# cryptostick-0v5.net
KiCad netlist of a schematic drawn in EAGLE
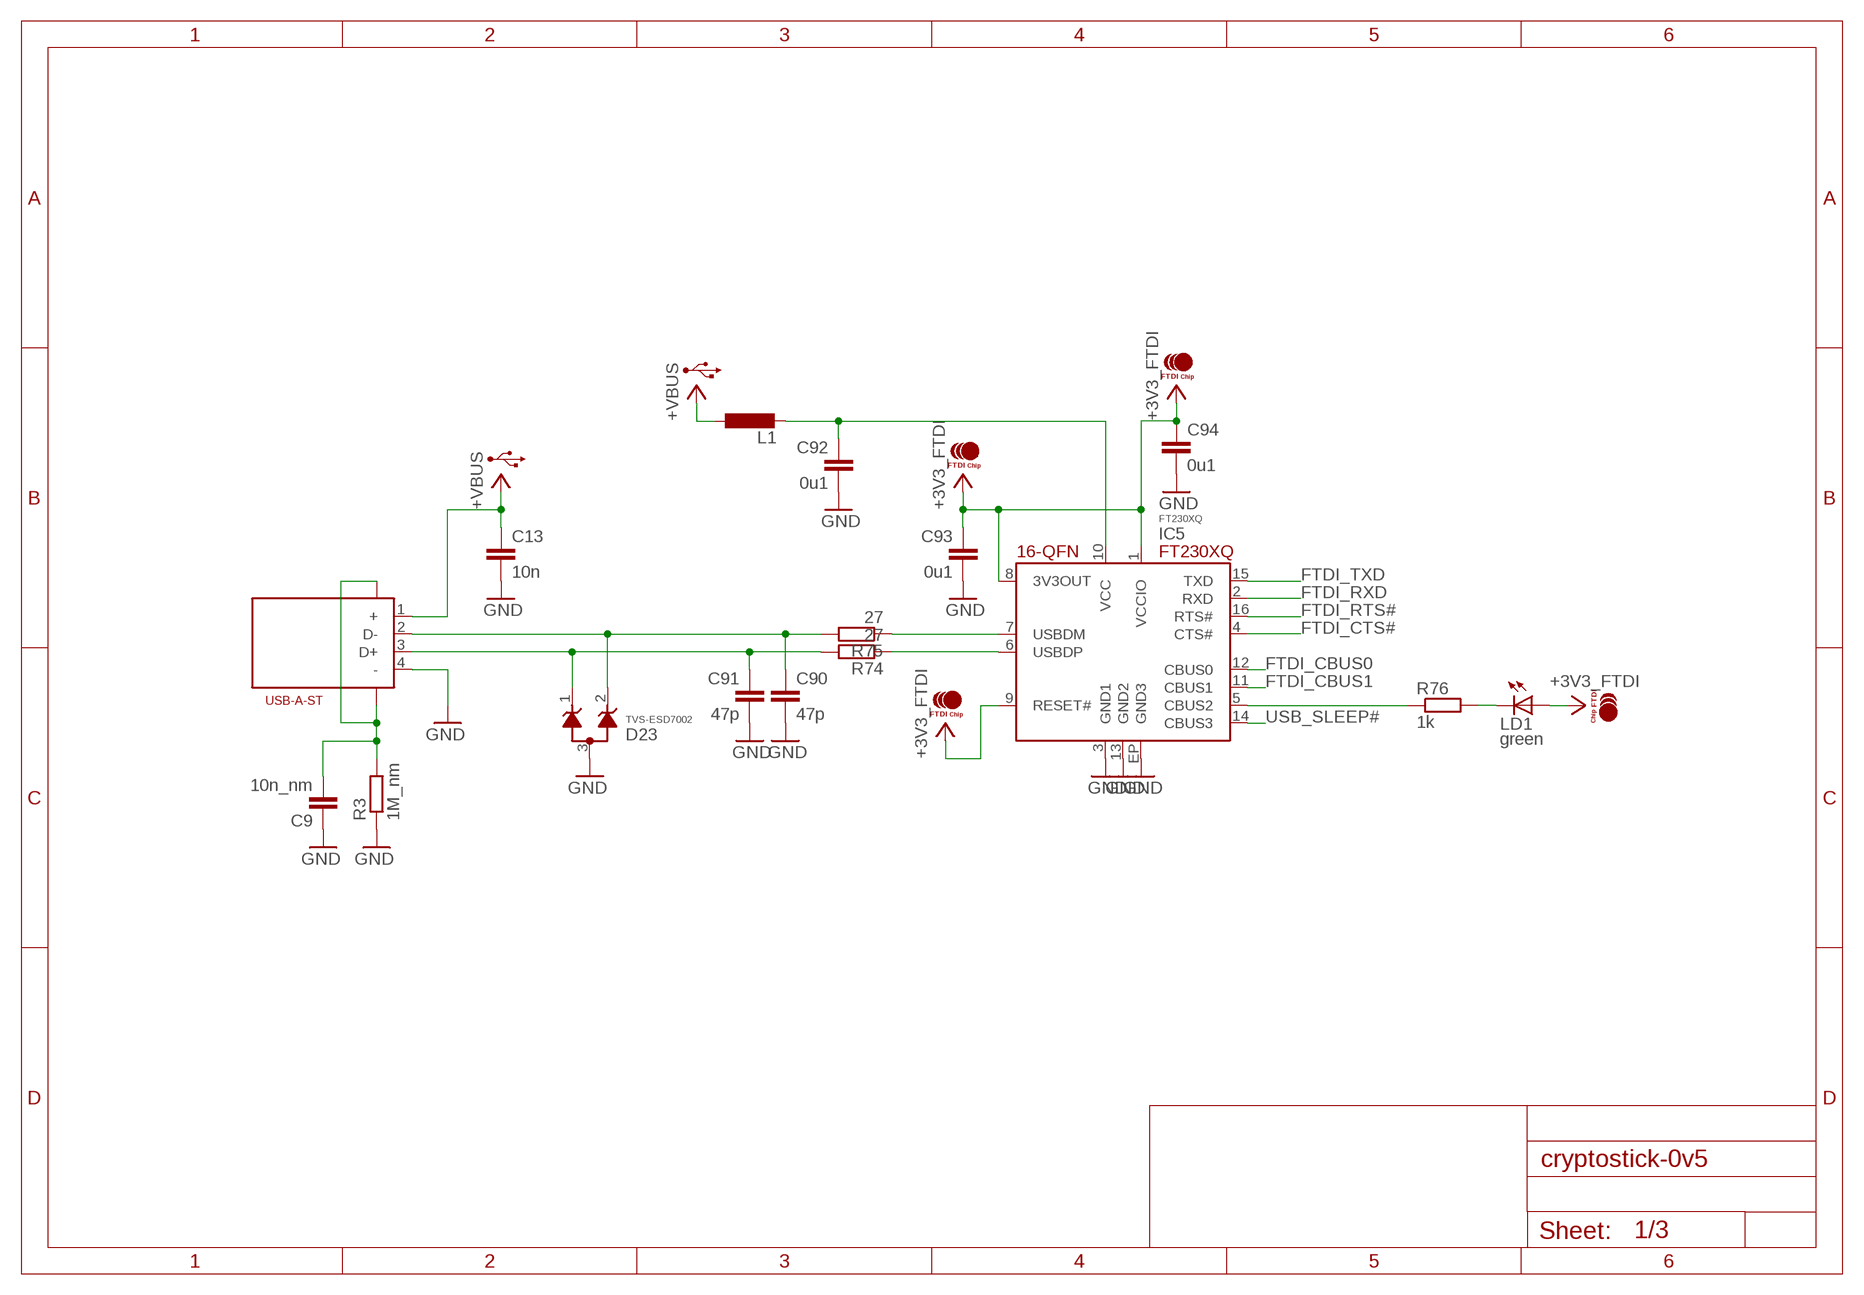
[diagram p0: schematic, sheet 1]
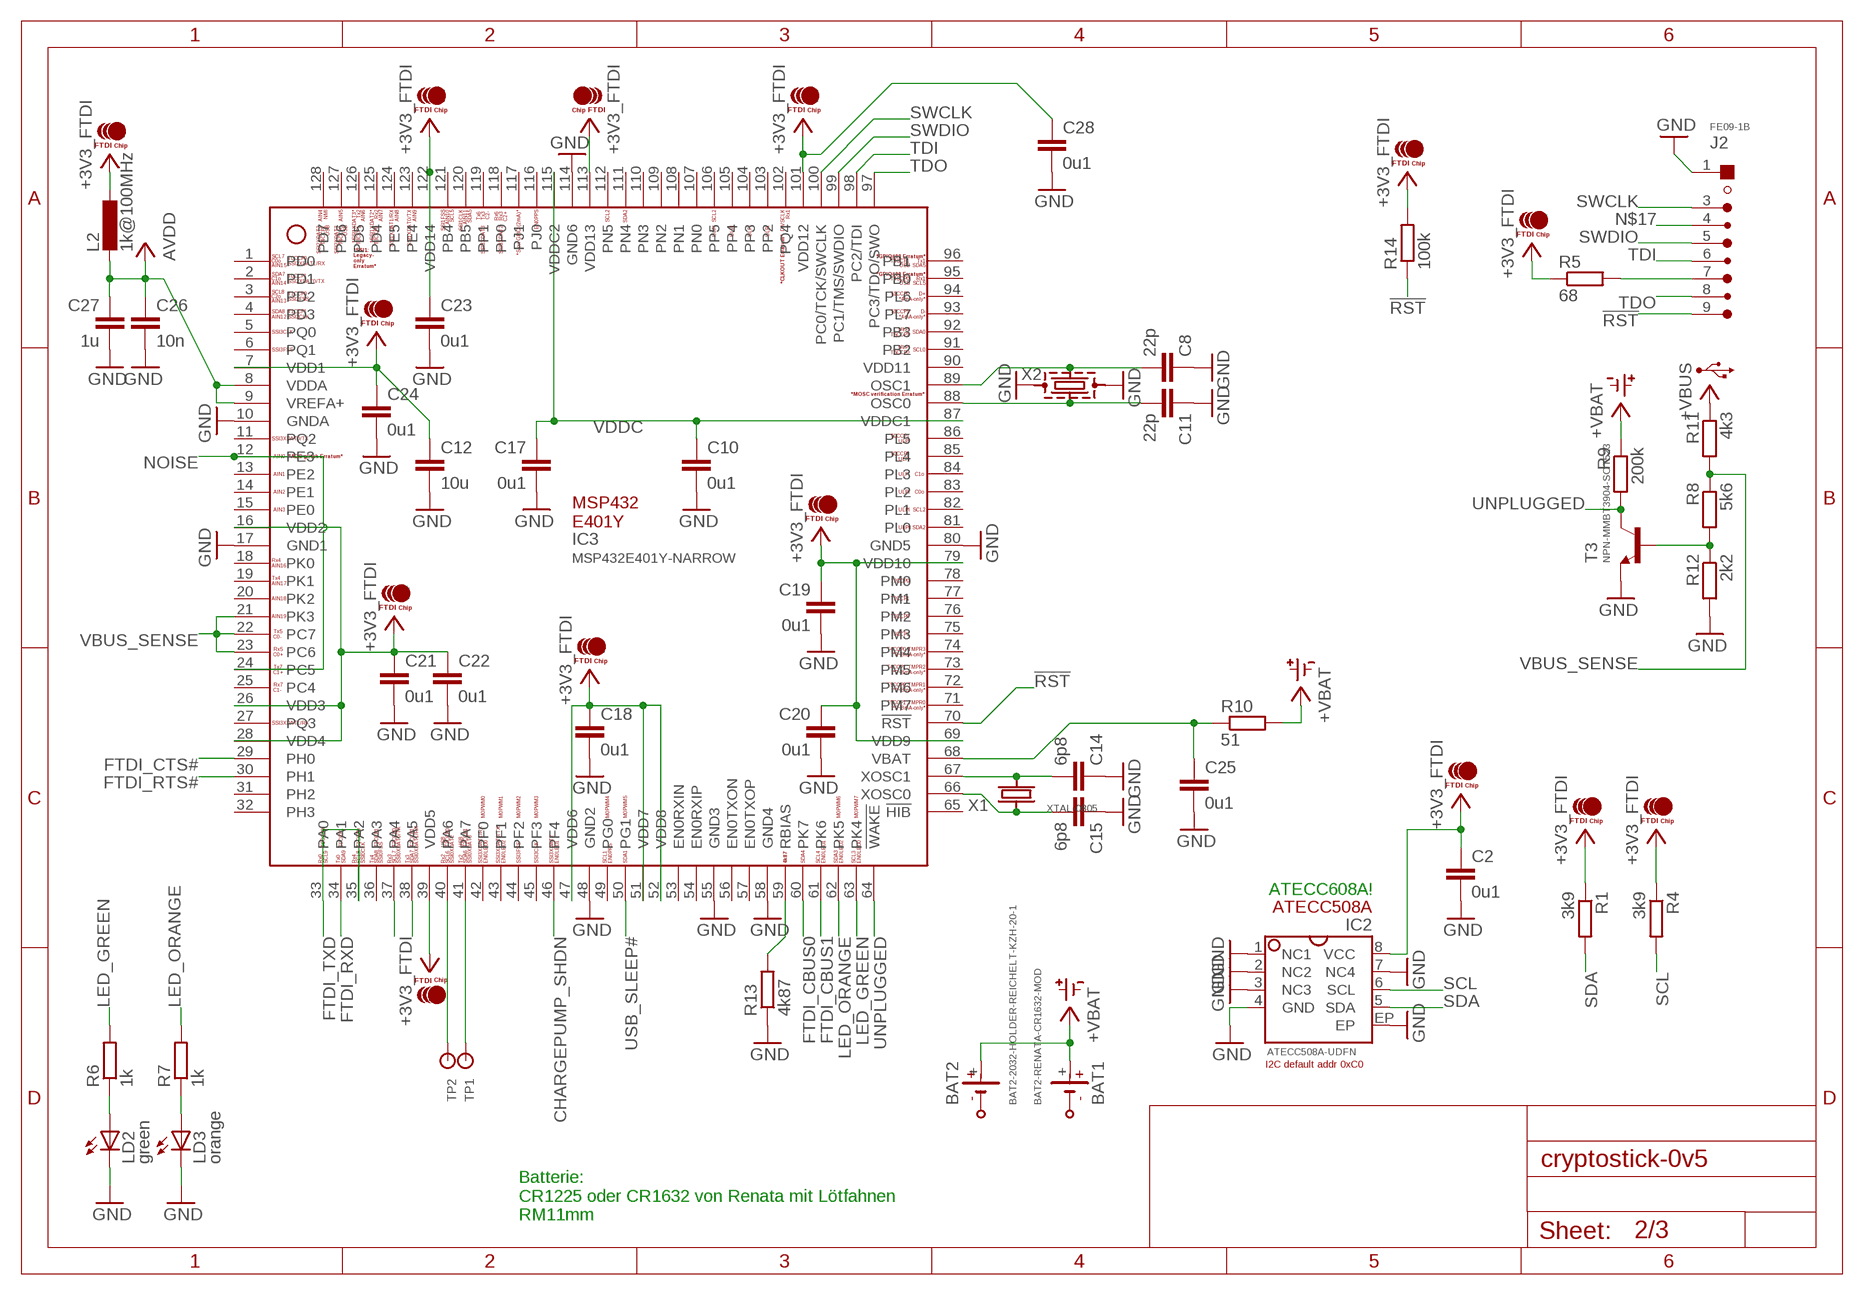
[diagram p1: schematic, sheet 2]
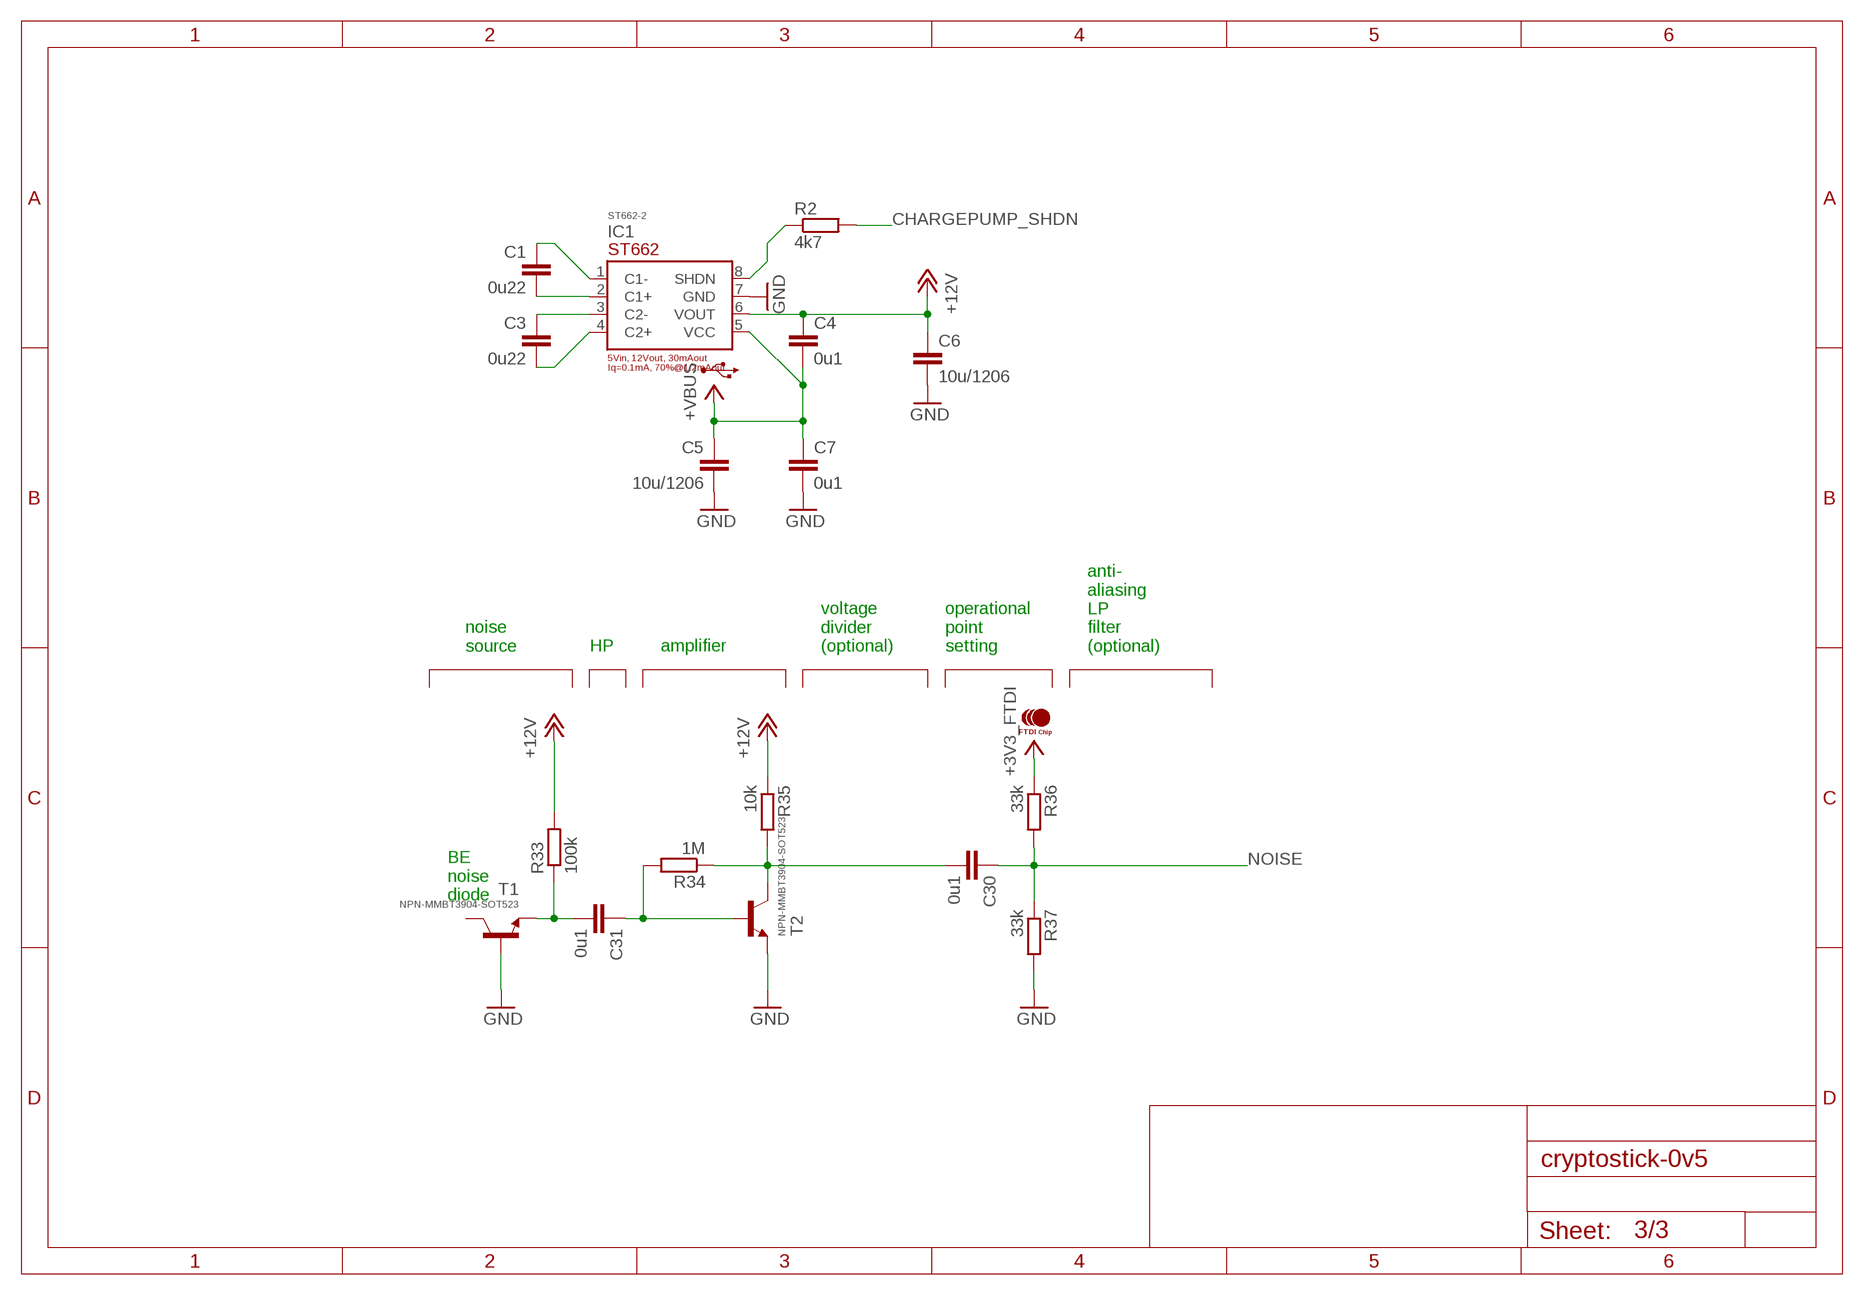
[diagram p2: schematic, sheet 3]

(export (version "E")
  (design (tool "Eeschema 10.0.6"))
  (components
    (comp (ref "C1")
      (value "0u22")
      (footprint "eagle-import:C0603")
      (libsource (lib "eagle-import") (part "C-EUC0603"))
    )
    (comp (ref "C3")
      (value "0u22")
      (footprint "eagle-import:C0603")
      (libsource (lib "eagle-import") (part "C-EUC0603"))
    )
    (comp (ref "C4")
      (value "0u1")
      (footprint "eagle-import:R0402-MCU")
      (libsource (lib "eagle-import") (part "C-EUR0402-MCU"))
    )
    (comp (ref "C5")
      (value "10u/1206")
      (footprint "eagle-import:C1206")
      (libsource (lib "eagle-import") (part "C-EUC1206"))
    )
    (comp (ref "C6")
      (value "10u/1206")
      (footprint "eagle-import:C1206")
      (libsource (lib "eagle-import") (part "C-EUC1206"))
    )
    (comp (ref "C7")
      (value "0u1")
      (footprint "eagle-import:R0402-MCU")
      (libsource (lib "eagle-import") (part "C-EUR0402-MCU"))
    )
    (comp (ref "C30")
      (value "0u1")
      (footprint "eagle-import:R0402-MCU")
      (libsource (lib "eagle-import") (part "C-EUR0402-MCU"))
    )
    (comp (ref "C31")
      (value "0u1")
      (footprint "eagle-import:R0402-MCU")
      (libsource (lib "eagle-import") (part "C-EUR0402-MCU"))
    )
    (comp (ref "IC1")
      (value "ST662-2")
      (footprint "eagle-import:8SOIC-2")
      (libsource (lib "eagle-import") (part "ST662-2"))
    )
    (comp (ref "R2")
      (value "4k7")
      (footprint "eagle-import:R0402-MCU")
      (libsource (lib "eagle-import") (part "R-EU_R0402-MCU"))
    )
    (comp (ref "R33")
      (value "100k")
      (footprint "eagle-import:R0402-MCU")
      (libsource (lib "eagle-import") (part "R-EU_R0402-MCU"))
    )
    (comp (ref "R34")
      (value "1M")
      (footprint "eagle-import:R0402-MCU")
      (libsource (lib "eagle-import") (part "R-EU_R0402-MCU"))
    )
    (comp (ref "R35")
      (value "10k")
      (footprint "eagle-import:R0402-MCU")
      (libsource (lib "eagle-import") (part "R-EU_R0402-MCU"))
    )
    (comp (ref "R36")
      (value "33k")
      (footprint "eagle-import:R0402-MCU")
      (libsource (lib "eagle-import") (part "R-EU_R0402-MCU"))
    )
    (comp (ref "R37")
      (value "33k")
      (footprint "eagle-import:R0402-MCU")
      (libsource (lib "eagle-import") (part "R-EU_R0402-MCU"))
    )
    (comp (ref "T1")
      (value "NPN-MMBT3904-SOT523")
      (footprint "eagle-import:SOT523")
      (libsource (lib "eagle-import") (part "NPN-MMBT3904-SOT523"))
    )
    (comp (ref "T2")
      (value "NPN-MMBT3904-SOT523")
      (footprint "eagle-import:SOT523")
      (libsource (lib "eagle-import") (part "NPN-MMBT3904-SOT523"))
    )
    (comp (ref "BAT1")
      (value "BAT2-RENATA-CR1632-MOD")
      (footprint "eagle-import:BAT2-RENATA-CR1632-MOD")
      (libsource (lib "eagle-import") (part "BAT2-RENATA-CR1632-MOD"))
    )
    (comp (ref "BAT2")
      (value "BAT2-2032-HOLDER-REICHELT-KZH-20-1")
      (footprint "eagle-import:BAT2-2032-HOLDER-REICHELT-KZH-20-1")
      (libsource (lib "eagle-import") (part "BAT2-2032-HOLDER-REICHELT-KZH-20-1"))
    )
    (comp (ref "C2")
      (value "0u1")
      (footprint "eagle-import:R0402-MCU")
      (libsource (lib "eagle-import") (part "C-EUR0402-MCU"))
    )
    (comp (ref "C8")
      (value "22p")
      (footprint "eagle-import:R0402-MCU")
      (libsource (lib "eagle-import") (part "C-EUR0402-MCU"))
    )
    (comp (ref "C10")
      (value "0u1")
      (footprint "eagle-import:R0402-MCU")
      (libsource (lib "eagle-import") (part "C-EUR0402-MCU"))
    )
    (comp (ref "C11")
      (value "22p")
      (footprint "eagle-import:R0402-MCU")
      (libsource (lib "eagle-import") (part "C-EUR0402-MCU"))
    )
    (comp (ref "C12")
      (value "10u")
      (footprint "eagle-import:R0603-MCU")
      (libsource (lib "eagle-import") (part "C-EUR0603-MCU"))
    )
    (comp (ref "C14")
      (value "6p8")
      (footprint "eagle-import:R0402-MCU")
      (libsource (lib "eagle-import") (part "C-EUR0402-MCU"))
    )
    (comp (ref "C15")
      (value "6p8")
      (footprint "eagle-import:R0402-MCU")
      (libsource (lib "eagle-import") (part "C-EUR0402-MCU"))
    )
    (comp (ref "C17")
      (value "0u1")
      (footprint "eagle-import:R0402-MCU")
      (libsource (lib "eagle-import") (part "C-EUR0402-MCU"))
    )
    (comp (ref "C18")
      (value "0u1")
      (footprint "eagle-import:R0402-MCU")
      (libsource (lib "eagle-import") (part "C-EUR0402-MCU"))
    )
    (comp (ref "C19")
      (value "0u1")
      (footprint "eagle-import:R0402-MCU")
      (libsource (lib "eagle-import") (part "C-EUR0402-MCU"))
    )
    (comp (ref "C20")
      (value "0u1")
      (footprint "eagle-import:R0402-MCU")
      (libsource (lib "eagle-import") (part "C-EUR0402-MCU"))
    )
    (comp (ref "C21")
      (value "0u1")
      (footprint "eagle-import:R0402-MCU")
      (libsource (lib "eagle-import") (part "C-EUR0402-MCU"))
    )
    (comp (ref "C22")
      (value "0u1")
      (footprint "eagle-import:R0402-MCU")
      (libsource (lib "eagle-import") (part "C-EUR0402-MCU"))
    )
    (comp (ref "C23")
      (value "0u1")
      (footprint "eagle-import:R0402-MCU")
      (libsource (lib "eagle-import") (part "C-EUR0402-MCU"))
    )
    (comp (ref "C24")
      (value "0u1")
      (footprint "eagle-import:R0402-MCU")
      (libsource (lib "eagle-import") (part "C-EUR0402-MCU"))
    )
    (comp (ref "C25")
      (value "0u1")
      (footprint "eagle-import:R0402-MCU")
      (libsource (lib "eagle-import") (part "C-EUR0402-MCU"))
    )
    (comp (ref "C26")
      (value "10n")
      (footprint "eagle-import:R0402-MCU")
      (libsource (lib "eagle-import") (part "C-EUR0402-MCU"))
    )
    (comp (ref "C27")
      (value "1u")
      (footprint "eagle-import:R0402-MCU")
      (libsource (lib "eagle-import") (part "C-EUR0402-MCU"))
    )
    (comp (ref "C28")
      (value "0u1")
      (footprint "eagle-import:R0402-MCU")
      (libsource (lib "eagle-import") (part "C-EUR0402-MCU"))
    )
    (comp (ref "IC2")
      (value "ATECC508A-UDFN")
      (footprint "eagle-import:8UDFN")
      (libsource (lib "eagle-import") (part "ATECC508A-UDFN"))
    )
    (comp (ref "IC3")
      (value "MSP432E401Y-NARROW")
      (footprint "eagle-import:128TQFP-MSP432E401Y-NARROW")
      (libsource (lib "eagle-import") (part "MSP432E401Y-NARROW"))
    )
    (comp (ref "J2")
      (value "FE09-1B")
      (footprint "eagle-import:FE09-1B")
      (libsource (lib "eagle-import") (part "FE09-1B"))
    )
    (comp (ref "L2")
      (value "1k@100MHz")
      (footprint "eagle-import:R0402-MCU")
      (libsource (lib "eagle-import") (part "L-EUR0402-MCU"))
    )
    (comp (ref "LD2")
      (value "green")
      (footprint "eagle-import:0603-SIDELED-RPI")
      (libsource (lib "eagle-import") (part "LED-0603-SIDELED-RPI"))
    )
    (comp (ref "LD3")
      (value "orange")
      (footprint "eagle-import:0603-SIDELED-RPI")
      (libsource (lib "eagle-import") (part "LED-0603-SIDELED-RPI"))
    )
    (comp (ref "R1")
      (value "3k9")
      (footprint "eagle-import:R0402-MCU")
      (libsource (lib "eagle-import") (part "R-EU_R0402-MCU"))
    )
    (comp (ref "R4")
      (value "3k9")
      (footprint "eagle-import:R0402-MCU")
      (libsource (lib "eagle-import") (part "R-EU_R0402-MCU"))
    )
    (comp (ref "R5")
      (value "68")
      (footprint "eagle-import:R0402-MCU")
      (libsource (lib "eagle-import") (part "R-EU_R0402-MCU"))
    )
    (comp (ref "R6")
      (value "1k")
      (footprint "eagle-import:R0402-MCU")
      (libsource (lib "eagle-import") (part "R-EU_R0402-MCU"))
    )
    (comp (ref "R7")
      (value "1k")
      (footprint "eagle-import:R0402-MCU")
      (libsource (lib "eagle-import") (part "R-EU_R0402-MCU"))
    )
    (comp (ref "R8")
      (value "5k6")
      (footprint "eagle-import:R0402-MCU")
      (libsource (lib "eagle-import") (part "R-EU_R0402-MCU"))
    )
    (comp (ref "R9")
      (value "200k")
      (footprint "eagle-import:R0402-MCU")
      (libsource (lib "eagle-import") (part "R-EU_R0402-MCU"))
    )
    (comp (ref "R10")
      (value "51")
      (footprint "eagle-import:R0402-MCU")
      (libsource (lib "eagle-import") (part "R-EU_R0402-MCU"))
    )
    (comp (ref "R11")
      (value "4k3")
      (footprint "eagle-import:R0402-MCU")
      (libsource (lib "eagle-import") (part "R-EU_R0402-MCU"))
    )
    (comp (ref "R12")
      (value "2k2")
      (footprint "eagle-import:R0402-MCU")
      (libsource (lib "eagle-import") (part "R-EU_R0402-MCU"))
    )
    (comp (ref "R13")
      (value "4k87")
      (footprint "eagle-import:R0402-MCU")
      (libsource (lib "eagle-import") (part "R-EU_R0402-MCU"))
    )
    (comp (ref "R14")
      (value "100k")
      (footprint "eagle-import:R0402-MCU")
      (libsource (lib "eagle-import") (part "R-EU_R0402-MCU"))
    )
    (comp (ref "T3")
      (value "NPN-MMBT3904-SOT523")
      (footprint "eagle-import:SOT523")
      (libsource (lib "eagle-import") (part "NPN-MMBT3904-SOT523"))
    )
    (comp (ref "TP1")
      (value "TP-SMT-1.5MM")
      (footprint "eagle-import:TP-SMT-1.5MM")
      (libsource (lib "eagle-import") (part "TP-SMT-1.5MM"))
    )
    (comp (ref "TP2")
      (value "TP-SMT-1.5MM")
      (footprint "eagle-import:TP-SMT-1.5MM")
      (libsource (lib "eagle-import") (part "TP-SMT-1.5MM"))
    )
    (comp (ref "X1")
      (value "XTAL-0805")
      (footprint "eagle-import:XTAL-32KHZ-0805")
      (libsource (lib "eagle-import") (part "XTAL-0805"))
    )
    (comp (ref "X2")
      (value "XTAL-2.0X1.6-MOD")
      (footprint "eagle-import:XTAL-2.0X1.6-MOD")
      (libsource (lib "eagle-import") (part "XTAL-2.0X1.6-MOD"))
    )
    (comp (ref "C9")
      (value "10n_nm")
      (footprint "eagle-import:C0603")
      (libsource (lib "eagle-import") (part "C-EUC0603"))
    )
    (comp (ref "C13")
      (value "10n")
      (footprint "eagle-import:R0402-MCU")
      (libsource (lib "eagle-import") (part "C-EUR0402-MCU"))
    )
    (comp (ref "C90")
      (value "47p")
      (footprint "eagle-import:R0402-MCU")
      (libsource (lib "eagle-import") (part "C-EUR0402-MCU"))
    )
    (comp (ref "C91")
      (value "47p")
      (footprint "eagle-import:R0402-MCU")
      (libsource (lib "eagle-import") (part "C-EUR0402-MCU"))
    )
    (comp (ref "C92")
      (value "0u1")
      (footprint "eagle-import:R0402-MCU")
      (libsource (lib "eagle-import") (part "C-EUR0402-MCU"))
    )
    (comp (ref "C93")
      (value "0u1")
      (footprint "eagle-import:R0402-MCU")
      (libsource (lib "eagle-import") (part "C-EUR0402-MCU"))
    )
    (comp (ref "C94")
      (value "0u1")
      (footprint "eagle-import:R0402-MCU")
      (libsource (lib "eagle-import") (part "C-EUR0402-MCU"))
    )
    (comp (ref "D23")
      (value "TVS-ESD7002")
      (footprint "eagle-import:SC70-3")
      (libsource (lib "eagle-import") (part "TVS-ESD7002"))
    )
    (comp (ref "IC5")
      (value "FT230XQ")
      (footprint "eagle-import:16QFN-FT230X")
      (libsource (lib "eagle-import") (part "FT230XQ"))
    )
    (comp (ref "J1")
      (value "USB-A-ST")
      (footprint "eagle-import:USB-A-ST")
      (libsource (lib "eagle-import") (part "USB-A-ST"))
    )
    (comp (ref "L1")
      (value "L-EUR0402-MCU")
      (footprint "eagle-import:R0402-MCU")
      (libsource (lib "eagle-import") (part "L-EUR0402-MCU"))
    )
    (comp (ref "LD1")
      (value "green")
      (footprint "eagle-import:0603-SIDELED-RPI")
      (libsource (lib "eagle-import") (part "LED-0603-SIDELED-RPI"))
    )
    (comp (ref "R3")
      (value "1M_nm")
      (footprint "eagle-import:R0603")
      (libsource (lib "eagle-import") (part "R-EU_R0603"))
    )
    (comp (ref "R74")
      (value "27")
      (footprint "eagle-import:R0402-MCU")
      (libsource (lib "eagle-import") (part "R-EU_R0402-MCU"))
    )
    (comp (ref "R75")
      (value "27")
      (footprint "eagle-import:R0402-MCU")
      (libsource (lib "eagle-import") (part "R-EU_R0402-MCU"))
    )
    (comp (ref "R76")
      (value "1k")
      (footprint "eagle-import:R0402-MCU")
      (libsource (lib "eagle-import") (part "R-EU_R0402-MCU"))
    )
  )
  (nets
    (net (code "1") (name "+3V3_FTDI") (class "Default")
      (node (ref "C12") (pin "1") (pinfunction "1_1") (pintype "passive"))
      (node (ref "C18") (pin "1") (pinfunction "1_1") (pintype "passive"))
      (node (ref "C19") (pin "1") (pinfunction "1_1") (pintype "passive"))
      (node (ref "C2") (pin "1") (pinfunction "1_1") (pintype "passive"))
      (node (ref "C20") (pin "1") (pinfunction "1_1") (pintype "passive"))
      (node (ref "C21") (pin "1") (pinfunction "1_1") (pintype "passive"))
      (node (ref "C22") (pin "1") (pinfunction "1_1") (pintype "passive"))
      (node (ref "C23") (pin "1") (pinfunction "1_1") (pintype "passive"))
      (node (ref "C24") (pin "1") (pinfunction "1_1") (pintype "passive"))
      (node (ref "C28") (pin "1") (pinfunction "1_1") (pintype "passive"))
      (node (ref "C93") (pin "1") (pinfunction "1_1") (pintype "passive"))
      (node (ref "C94") (pin "1") (pinfunction "1_1") (pintype "passive"))
      (node (ref "IC2") (pin "8") (pinfunction "VCC_8") (pintype "bidirectional"))
      (node (ref "IC3") (pin "101") (pinfunction "VDD12_101") (pintype "bidirectional"))
      (node (ref "IC3") (pin "113") (pinfunction "VDD13_113") (pintype "bidirectional"))
      (node (ref "IC3") (pin "122") (pinfunction "VDD14_122") (pintype "bidirectional"))
      (node (ref "IC3") (pin "16") (pinfunction "VDD2_16") (pintype "bidirectional"))
      (node (ref "IC3") (pin "26") (pinfunction "VDD3_26") (pintype "bidirectional"))
      (node (ref "IC3") (pin "28") (pinfunction "VDD4_28") (pintype "bidirectional"))
      (node (ref "IC3") (pin "39") (pinfunction "VDD5_39") (pintype "bidirectional"))
      (node (ref "IC3") (pin "47") (pinfunction "VDD6_47") (pintype "bidirectional"))
      (node (ref "IC3") (pin "51") (pinfunction "VDD7_51") (pintype "bidirectional"))
      (node (ref "IC3") (pin "52") (pinfunction "VDD8_52") (pintype "bidirectional"))
      (node (ref "IC3") (pin "69") (pinfunction "VDD9_69") (pintype "bidirectional"))
      (node (ref "IC3") (pin "7") (pinfunction "VDD1_7") (pintype "bidirectional"))
      (node (ref "IC3") (pin "79") (pinfunction "VDD10_79") (pintype "bidirectional"))
      (node (ref "IC5") (pin "1") (pinfunction "VCCIO_1") (pintype "bidirectional"))
      (node (ref "IC5") (pin "8") (pinfunction "3V3OUT_8") (pintype "bidirectional"))
      (node (ref "IC5") (pin "9") (pinfunction "RESET#_9") (pintype "bidirectional"))
      (node (ref "L2") (pin "1") (pinfunction "1_1") (pintype "passive"))
      (node (ref "LD1") (pin "A") (pinfunction "A_A") (pintype "passive"))
      (node (ref "R1") (pin "1") (pinfunction "1_1") (pintype "passive"))
      (node (ref "R14") (pin "2") (pinfunction "2_2") (pintype "passive"))
      (node (ref "R36") (pin "1") (pinfunction "1_1") (pintype "passive"))
      (node (ref "R4") (pin "1") (pinfunction "1_1") (pintype "passive"))
      (node (ref "R5") (pin "1") (pinfunction "1_1") (pintype "passive"))
    )
    (net (code "2") (name "+12V") (class "Default")
      (node (ref "C4") (pin "1") (pinfunction "1_1") (pintype "passive"))
      (node (ref "C6") (pin "1") (pinfunction "1_1") (pintype "passive"))
      (node (ref "IC1") (pin "6") (pinfunction "VOUT_6") (pintype "bidirectional"))
      (node (ref "R33") (pin "2") (pinfunction "2_2") (pintype "passive"))
      (node (ref "R35") (pin "1") (pinfunction "1_1") (pintype "passive"))
    )
    (net (code "3") (name "+VBAT") (class "Default")
      (node (ref "BAT1") (pin "+") (pinfunction "+_+") (pintype "bidirectional"))
      (node (ref "BAT2") (pin "+") (pinfunction "+_+") (pintype "bidirectional"))
      (node (ref "R10") (pin "2") (pinfunction "2_2") (pintype "passive"))
      (node (ref "R9") (pin "1") (pinfunction "1_1") (pintype "passive"))
    )
    (net (code "4") (name "+VBUS") (class "Default")
      (node (ref "C13") (pin "1") (pinfunction "1_1") (pintype "passive"))
      (node (ref "C4") (pin "2") (pinfunction "2_2") (pintype "passive"))
      (node (ref "C5") (pin "1") (pinfunction "1_1") (pintype "passive"))
      (node (ref "C7") (pin "1") (pinfunction "1_1") (pintype "passive"))
      (node (ref "IC1") (pin "5") (pinfunction "VCC_5") (pintype "bidirectional"))
      (node (ref "J1") (pin "1") (pinfunction "+_1") (pintype "bidirectional"))
      (node (ref "L1") (pin "1") (pinfunction "1_1") (pintype "passive"))
      (node (ref "R11") (pin "1") (pinfunction "1_1") (pintype "passive"))
    )
    (net (code "5") (name "AVDD") (class "Default")
      (node (ref "C26") (pin "1") (pinfunction "1_1") (pintype "passive"))
      (node (ref "C27") (pin "1") (pinfunction "1_1") (pintype "passive"))
      (node (ref "IC3") (pin "8") (pinfunction "VDDA_8") (pintype "bidirectional"))
      (node (ref "IC3") (pin "9") (pinfunction "VREFA+_9") (pintype "bidirectional"))
      (node (ref "L2") (pin "2") (pinfunction "2_2") (pintype "passive"))
    )
    (net (code "6") (name "CHARGEPUMP_SHDN") (class "Default")
      (node (ref "IC3") (pin "46") (pinfunction "PF4_46") (pintype "bidirectional"))
      (node (ref "R2") (pin "2") (pinfunction "2_2") (pintype "passive"))
    )
    (net (code "7") (name "DBG_RXD") (class "Default")
      (node (ref "IC3") (pin "40") (pinfunction "PA6_40") (pintype "bidirectional"))
      (node (ref "IC3") (pin "74") (pinfunction "PM4_74") (pintype "bidirectional"))
      (node (ref "TP2") (pin "1") (pinfunction "1_1") (pintype "bidirectional"))
    )
    (net (code "8") (name "DBG_TXD") (class "Default")
      (node (ref "IC3") (pin "41") (pinfunction "PA7_41") (pintype "bidirectional"))
      (node (ref "IC3") (pin "73") (pinfunction "PM5_73") (pintype "bidirectional"))
      (node (ref "TP1") (pin "1") (pinfunction "1_1") (pintype "bidirectional"))
    )
    (net (code "9") (name "FTDI_CBUS0") (class "Default")
      (node (ref "IC3") (pin "60") (pinfunction "PK7_60") (pintype "bidirectional"))
      (node (ref "IC5") (pin "12") (pinfunction "CBUS0_12") (pintype "bidirectional"))
    )
    (net (code "10") (name "FTDI_CBUS1") (class "Default")
      (node (ref "IC3") (pin "61") (pinfunction "PK6_61") (pintype "bidirectional"))
      (node (ref "IC5") (pin "11") (pinfunction "CBUS1_11") (pintype "bidirectional"))
    )
    (net (code "11") (name "FTDI_CTS#") (class "Default")
      (node (ref "IC3") (pin "29") (pinfunction "PH0_29") (pintype "bidirectional"))
      (node (ref "IC5") (pin "4") (pinfunction "CTS#_4") (pintype "bidirectional"))
    )
    (net (code "12") (name "FTDI_RTS#") (class "Default")
      (node (ref "IC3") (pin "30") (pinfunction "PH1_30") (pintype "bidirectional"))
      (node (ref "IC5") (pin "16") (pinfunction "RTS#_16") (pintype "bidirectional"))
    )
    (net (code "13") (name "FTDI_RXD") (class "Default")
      (node (ref "IC3") (pin "34") (pinfunction "PA1_34") (pintype "bidirectional"))
      (node (ref "IC5") (pin "2") (pinfunction "RXD_2") (pintype "bidirectional"))
    )
    (net (code "14") (name "FTDI_TXD") (class "Default")
      (node (ref "IC3") (pin "33") (pinfunction "PA0_33") (pintype "bidirectional"))
      (node (ref "IC3") (pin "35") (pinfunction "PA2_35") (pintype "bidirectional"))
      (node (ref "IC5") (pin "15") (pinfunction "TXD_15") (pintype "bidirectional"))
    )
    (net (code "15") (name "GND") (class "Default")
      (node (ref "C10") (pin "2") (pinfunction "2_2") (pintype "passive"))
      (node (ref "C11") (pin "1") (pinfunction "1_1") (pintype "passive"))
      (node (ref "C12") (pin "2") (pinfunction "2_2") (pintype "passive"))
      (node (ref "C13") (pin "2") (pinfunction "2_2") (pintype "passive"))
      (node (ref "C14") (pin "1") (pinfunction "1_1") (pintype "passive"))
      (node (ref "C15") (pin "1") (pinfunction "1_1") (pintype "passive"))
      (node (ref "C17") (pin "2") (pinfunction "2_2") (pintype "passive"))
      (node (ref "C18") (pin "2") (pinfunction "2_2") (pintype "passive"))
      (node (ref "C19") (pin "2") (pinfunction "2_2") (pintype "passive"))
      (node (ref "C2") (pin "2") (pinfunction "2_2") (pintype "passive"))
      (node (ref "C20") (pin "2") (pinfunction "2_2") (pintype "passive"))
      (node (ref "C21") (pin "2") (pinfunction "2_2") (pintype "passive"))
      (node (ref "C22") (pin "2") (pinfunction "2_2") (pintype "passive"))
      (node (ref "C23") (pin "2") (pinfunction "2_2") (pintype "passive"))
      (node (ref "C24") (pin "2") (pinfunction "2_2") (pintype "passive"))
      (node (ref "C25") (pin "2") (pinfunction "2_2") (pintype "passive"))
      (node (ref "C26") (pin "2") (pinfunction "2_2") (pintype "passive"))
      (node (ref "C27") (pin "2") (pinfunction "2_2") (pintype "passive"))
      (node (ref "C28") (pin "2") (pinfunction "2_2") (pintype "passive"))
      (node (ref "C5") (pin "2") (pinfunction "2_2") (pintype "passive"))
      (node (ref "C6") (pin "2") (pinfunction "2_2") (pintype "passive"))
      (node (ref "C7") (pin "2") (pinfunction "2_2") (pintype "passive"))
      (node (ref "C8") (pin "1") (pinfunction "1_1") (pintype "passive"))
      (node (ref "C9") (pin "1") (pinfunction "1_1") (pintype "passive"))
      (node (ref "C90") (pin "2") (pinfunction "2_2") (pintype "passive"))
      (node (ref "C91") (pin "2") (pinfunction "2_2") (pintype "passive"))
      (node (ref "C92") (pin "2") (pinfunction "2_2") (pintype "passive"))
      (node (ref "C93") (pin "2") (pinfunction "2_2") (pintype "passive"))
      (node (ref "C94") (pin "2") (pinfunction "2_2") (pintype "passive"))
      (node (ref "D23") (pin "3") (pinfunction "3_3") (pintype "bidirectional"))
      (node (ref "IC1") (pin "7") (pinfunction "GND_7") (pintype "bidirectional"))
      (node (ref "IC2") (pin "1") (pinfunction "NC1_1") (pintype "bidirectional"))
      (node (ref "IC2") (pin "2") (pinfunction "NC2_2") (pintype "bidirectional"))
      (node (ref "IC2") (pin "3") (pinfunction "NC3_3") (pintype "bidirectional"))
      (node (ref "IC2") (pin "4") (pinfunction "GND_4") (pintype "bidirectional"))
      (node (ref "IC2") (pin "7") (pinfunction "NC4_7") (pintype "bidirectional"))
      (node (ref "IC2") (pin "EP") (pinfunction "EP_EP") (pintype "bidirectional"))
      (node (ref "IC3") (pin "10") (pinfunction "GNDA_10") (pintype "bidirectional"))
      (node (ref "IC3") (pin "114") (pinfunction "GND6_114") (pintype "bidirectional"))
      (node (ref "IC3") (pin "17") (pinfunction "GND1_17") (pintype "bidirectional"))
      (node (ref "IC3") (pin "48") (pinfunction "GND2_48") (pintype "bidirectional"))
      (node (ref "IC3") (pin "55") (pinfunction "GND3_55") (pintype "bidirectional"))
      (node (ref "IC3") (pin "58") (pinfunction "GND4_58") (pintype "bidirectional"))
      (node (ref "IC3") (pin "80") (pinfunction "GND5_80") (pintype "bidirectional"))
      (node (ref "IC5") (pin "13") (pinfunction "GND2_13") (pintype "bidirectional"))
      (node (ref "IC5") (pin "3") (pinfunction "GND1_3") (pintype "bidirectional"))
      (node (ref "IC5") (pin "EP") (pinfunction "GND3_EP") (pintype "bidirectional"))
      (node (ref "J1") (pin "4") (pinfunction "-_4") (pintype "bidirectional"))
      (node (ref "J2") (pin "1") (pinfunction "1_1") (pintype "bidirectional"))
      (node (ref "LD2") (pin "C") (pinfunction "C_C") (pintype "passive"))
      (node (ref "LD3") (pin "C") (pinfunction "C_C") (pintype "passive"))
      (node (ref "R12") (pin "2") (pinfunction "2_2") (pintype "passive"))
      (node (ref "R13") (pin "1") (pinfunction "1_1") (pintype "passive"))
      (node (ref "R3") (pin "1") (pinfunction "1_1") (pintype "passive"))
      (node (ref "R37") (pin "2") (pinfunction "2_2") (pintype "passive"))
      (node (ref "T1") (pin "1") (pinfunction "B_1") (pintype "passive"))
      (node (ref "T2") (pin "2") (pinfunction "E_2") (pintype "passive"))
      (node (ref "T3") (pin "2") (pinfunction "E_2") (pintype "passive"))
      (node (ref "X2") (pin "2") (pinfunction "GND1_2") (pintype "bidirectional"))
      (node (ref "X2") (pin "4") (pinfunction "GND2_4") (pintype "bidirectional"))
    )
    (net (code "16") (name "LED_GREEN") (class "Default")
      (node (ref "IC3") (pin "63") (pinfunction "PK4_63") (pintype "bidirectional"))
      (node (ref "R6") (pin "2") (pinfunction "2_2") (pintype "passive"))
    )
    (net (code "17") (name "LED_ORANGE") (class "Default")
      (node (ref "IC3") (pin "62") (pinfunction "PK5_62") (pintype "bidirectional"))
      (node (ref "R7") (pin "2") (pinfunction "2_2") (pintype "passive"))
    )
    (net (code "18") (name "N$17") (class "Default")
      (node (ref "J2") (pin "4") (pinfunction "4_4") (pintype "bidirectional"))
    )
    (net (code "19") (name "NOISE") (class "Default")
      (node (ref "C30") (pin "1") (pinfunction "1_1") (pintype "passive"))
      (node (ref "IC3") (pin "12") (pinfunction "PE3_12") (pintype "bidirectional"))
      (node (ref "IC3") (pin "24") (pinfunction "PC5_24") (pintype "bidirectional"))
      (node (ref "R36") (pin "2") (pinfunction "2_2") (pintype "passive"))
      (node (ref "R37") (pin "1") (pinfunction "1_1") (pintype "passive"))
    )
    (net (code "20") (name "Net-(C9-Pad2)") (class "Default")
      (node (ref "C9") (pin "2") (pinfunction "2_2") (pintype "passive"))
      (node (ref "J1") (pin "SH1") (pinfunction "SH1_SH1") (pintype "bidirectional"))
      (node (ref "J1") (pin "SH2") (pinfunction "SH2_SH2") (pintype "bidirectional"))
      (node (ref "R3") (pin "2") (pinfunction "2_2") (pintype "passive"))
    )
    (net (code "21") (name "Net-(IC1-C1+)") (class "Default")
      (node (ref "C1") (pin "2") (pinfunction "2_2") (pintype "passive"))
      (node (ref "IC1") (pin "2") (pinfunction "C1+_2") (pintype "bidirectional"))
    )
    (net (code "22") (name "Net-(IC1-C1-)") (class "Default")
      (node (ref "C1") (pin "1") (pinfunction "1_1") (pintype "passive"))
      (node (ref "IC1") (pin "1") (pinfunction "C1-_1") (pintype "bidirectional"))
    )
    (net (code "23") (name "Net-(IC1-C2+)") (class "Default")
      (node (ref "C3") (pin "2") (pinfunction "2_2") (pintype "passive"))
      (node (ref "IC1") (pin "4") (pinfunction "C2+_4") (pintype "bidirectional"))
    )
    (net (code "24") (name "Net-(IC1-C2-)") (class "Default")
      (node (ref "C3") (pin "1") (pinfunction "1_1") (pintype "passive"))
      (node (ref "IC1") (pin "3") (pinfunction "C2-_3") (pintype "bidirectional"))
    )
    (net (code "25") (name "Net-(IC1-SHDN)") (class "Default")
      (node (ref "IC1") (pin "8") (pinfunction "SHDN_8") (pintype "bidirectional"))
      (node (ref "R2") (pin "1") (pinfunction "1_1") (pintype "passive"))
    )
    (net (code "26") (name "Net-(IC3-OSC0)") (class "Default")
      (node (ref "C11") (pin "2") (pinfunction "2_2") (pintype "passive"))
      (node (ref "IC3") (pin "88") (pinfunction "OSC0_88") (pintype "bidirectional"))
      (node (ref "X2") (pin "1") (pinfunction "1_1") (pintype "bidirectional"))
    )
    (net (code "27") (name "Net-(IC3-OSC1)") (class "Default")
      (node (ref "C8") (pin "2") (pinfunction "2_2") (pintype "passive"))
      (node (ref "IC3") (pin "89") (pinfunction "OSC1_89") (pintype "bidirectional"))
      (node (ref "X2") (pin "3") (pinfunction "2_3") (pintype "bidirectional"))
    )
    (net (code "28") (name "Net-(IC3-RBIAS)") (class "Default")
      (node (ref "IC3") (pin "59") (pinfunction "RBIAS_59") (pintype "bidirectional"))
      (node (ref "R13") (pin "2") (pinfunction "2_2") (pintype "passive"))
    )
    (net (code "29") (name "Net-(IC3-VBAT)") (class "Default")
      (node (ref "C25") (pin "1") (pinfunction "1_1") (pintype "passive"))
      (node (ref "IC3") (pin "68") (pinfunction "VBAT_68") (pintype "bidirectional"))
      (node (ref "R10") (pin "1") (pinfunction "1_1") (pintype "passive"))
    )
    (net (code "30") (name "Net-(IC3-XOSC0)") (class "Default")
      (node (ref "C15") (pin "2") (pinfunction "2_2") (pintype "passive"))
      (node (ref "IC3") (pin "66") (pinfunction "XOSC0_66") (pintype "bidirectional"))
      (node (ref "X1") (pin "P$2") (pinfunction "2_P$2") (pintype "bidirectional"))
    )
    (net (code "31") (name "Net-(IC3-XOSC1)") (class "Default")
      (node (ref "C14") (pin "2") (pinfunction "2_2") (pintype "passive"))
      (node (ref "IC3") (pin "67") (pinfunction "XOSC1_67") (pintype "bidirectional"))
      (node (ref "X1") (pin "P$1") (pinfunction "1_P$1") (pintype "bidirectional"))
    )
    (net (code "32") (name "Net-(IC5-CBUS2)") (class "Default")
      (node (ref "IC5") (pin "5") (pinfunction "CBUS2_5") (pintype "bidirectional"))
      (node (ref "R76") (pin "1") (pinfunction "1_1") (pintype "passive"))
    )
    (net (code "33") (name "Net-(IC5-USBDM)") (class "Default")
      (node (ref "IC5") (pin "7") (pinfunction "USBDM_7") (pintype "bidirectional"))
      (node (ref "R75") (pin "1") (pinfunction "1_1") (pintype "passive"))
    )
    (net (code "34") (name "Net-(IC5-USBDP)") (class "Default")
      (node (ref "IC5") (pin "6") (pinfunction "USBDP_6") (pintype "bidirectional"))
      (node (ref "R74") (pin "1") (pinfunction "1_1") (pintype "passive"))
    )
    (net (code "35") (name "Net-(IC5-VCC)") (class "Default")
      (node (ref "C92") (pin "1") (pinfunction "1_1") (pintype "passive"))
      (node (ref "IC5") (pin "10") (pinfunction "VCC_10") (pintype "bidirectional"))
      (node (ref "L1") (pin "2") (pinfunction "2_2") (pintype "passive"))
    )
    (net (code "36") (name "Net-(J1-D+)") (class "Default")
      (node (ref "C91") (pin "1") (pinfunction "1_1") (pintype "passive"))
      (node (ref "D23") (pin "1") (pinfunction "1_1") (pintype "bidirectional"))
      (node (ref "J1") (pin "3") (pinfunction "D+_3") (pintype "bidirectional"))
      (node (ref "R74") (pin "2") (pinfunction "2_2") (pintype "passive"))
    )
    (net (code "37") (name "Net-(J1-D-)") (class "Default")
      (node (ref "C90") (pin "1") (pinfunction "1_1") (pintype "passive"))
      (node (ref "D23") (pin "2") (pinfunction "2_2") (pintype "bidirectional"))
      (node (ref "J1") (pin "2") (pinfunction "D-_2") (pintype "bidirectional"))
      (node (ref "R75") (pin "2") (pinfunction "2_2") (pintype "passive"))
    )
    (net (code "38") (name "Net-(J2-Pad7)") (class "Default")
      (node (ref "J2") (pin "7") (pinfunction "7_7") (pintype "bidirectional"))
      (node (ref "R5") (pin "2") (pinfunction "2_2") (pintype "passive"))
    )
    (net (code "39") (name "Net-(LD1-PadC)") (class "Default")
      (node (ref "LD1") (pin "C") (pinfunction "C_C") (pintype "passive"))
      (node (ref "R76") (pin "2") (pinfunction "2_2") (pintype "passive"))
    )
    (net (code "40") (name "Net-(LD2-PadA)") (class "Default")
      (node (ref "LD2") (pin "A") (pinfunction "A_A") (pintype "passive"))
      (node (ref "R6") (pin "1") (pinfunction "1_1") (pintype "passive"))
    )
    (net (code "41") (name "Net-(LD3-PadA)") (class "Default")
      (node (ref "LD3") (pin "A") (pinfunction "A_A") (pintype "passive"))
      (node (ref "R7") (pin "1") (pinfunction "1_1") (pintype "passive"))
    )
    (net (code "42") (name "Net-(T1-E)") (class "Default")
      (node (ref "C31") (pin "2") (pinfunction "2_2") (pintype "passive"))
      (node (ref "R33") (pin "1") (pinfunction "1_1") (pintype "passive"))
      (node (ref "T1") (pin "2") (pinfunction "E_2") (pintype "passive"))
    )
    (net (code "43") (name "Net-(T2-B)") (class "Default")
      (node (ref "C31") (pin "1") (pinfunction "1_1") (pintype "passive"))
      (node (ref "R34") (pin "2") (pinfunction "2_2") (pintype "passive"))
      (node (ref "T2") (pin "1") (pinfunction "B_1") (pintype "passive"))
    )
    (net (code "44") (name "Net-(T2-C)") (class "Default")
      (node (ref "C30") (pin "2") (pinfunction "2_2") (pintype "passive"))
      (node (ref "R34") (pin "1") (pinfunction "1_1") (pintype "passive"))
      (node (ref "R35") (pin "2") (pinfunction "2_2") (pintype "passive"))
      (node (ref "T2") (pin "3") (pinfunction "C_3") (pintype "passive"))
    )
    (net (code "45") (name "Net-(T3-B)") (class "Default")
      (node (ref "R12") (pin "1") (pinfunction "1_1") (pintype "passive"))
      (node (ref "R8") (pin "2") (pinfunction "2_2") (pintype "passive"))
      (node (ref "T3") (pin "1") (pinfunction "B_1") (pintype "passive"))
    )
    (net (code "46") (name "SCL") (class "Default")
      (node (ref "IC2") (pin "6") (pinfunction "SCL_6") (pintype "bidirectional"))
      (node (ref "IC3") (pin "37") (pinfunction "PA4_37") (pintype "bidirectional"))
      (node (ref "R4") (pin "2") (pinfunction "2_2") (pintype "passive"))
    )
    (net (code "47") (name "SDA") (class "Default")
      (node (ref "IC2") (pin "5") (pinfunction "SDA_5") (pintype "bidirectional"))
      (node (ref "IC3") (pin "38") (pinfunction "PA5_38") (pintype "bidirectional"))
      (node (ref "R1") (pin "2") (pinfunction "2_2") (pintype "passive"))
    )
    (net (code "48") (name "SWCLK") (class "Default")
      (node (ref "IC3") (pin "100") (pinfunction "PC0/TCK/SWCLK_100") (pintype "bidirectional"))
      (node (ref "J2") (pin "3") (pinfunction "3_3") (pintype "bidirectional"))
    )
    (net (code "49") (name "SWDIO") (class "Default")
      (node (ref "IC3") (pin "99") (pinfunction "PC1/TMS/SWDIO_99") (pintype "bidirectional"))
      (node (ref "J2") (pin "5") (pinfunction "5_5") (pintype "bidirectional"))
    )
    (net (code "50") (name "TDI") (class "Default")
      (node (ref "IC3") (pin "98") (pinfunction "PC2/TDI_98") (pintype "bidirectional"))
      (node (ref "J2") (pin "6") (pinfunction "6_6") (pintype "bidirectional"))
    )
    (net (code "51") (name "TDO") (class "Default")
      (node (ref "IC3") (pin "97") (pinfunction "PC3/TDO/SWO_97") (pintype "bidirectional"))
      (node (ref "J2") (pin "8") (pinfunction "8_8") (pintype "bidirectional"))
    )
    (net (code "52") (name "UNPLUGGED") (class "Default")
      (node (ref "IC3") (pin "64") (pinfunction "~{WAKE}_64") (pintype "bidirectional"))
      (node (ref "IC3") (pin "72") (pinfunction "PM6_72") (pintype "bidirectional"))
      (node (ref "R9") (pin "2") (pinfunction "2_2") (pintype "passive"))
      (node (ref "T3") (pin "3") (pinfunction "C_3") (pintype "passive"))
    )
    (net (code "53") (name "USB_SLEEP#") (class "Default")
      (node (ref "IC3") (pin "50") (pinfunction "PG1_50") (pintype "bidirectional"))
      (node (ref "IC5") (pin "14") (pinfunction "CBUS3_14") (pintype "bidirectional"))
    )
    (net (code "54") (name "VBUS_SENSE") (class "Default")
      (node (ref "IC3") (pin "21") (pinfunction "PK3_21") (pintype "bidirectional"))
      (node (ref "IC3") (pin "22") (pinfunction "PC7_22") (pintype "bidirectional"))
      (node (ref "IC3") (pin "23") (pinfunction "PC6_23") (pintype "bidirectional"))
      (node (ref "R11") (pin "2") (pinfunction "2_2") (pintype "passive"))
      (node (ref "R8") (pin "1") (pinfunction "1_1") (pintype "passive"))
    )
    (net (code "55") (name "VDDC") (class "Default")
      (node (ref "C10") (pin "1") (pinfunction "1_1") (pintype "passive"))
      (node (ref "C17") (pin "1") (pinfunction "1_1") (pintype "passive"))
      (node (ref "IC3") (pin "115") (pinfunction "VDDC2_115") (pintype "bidirectional"))
      (node (ref "IC3") (pin "87") (pinfunction "VDDC1_87") (pintype "bidirectional"))
    )
    (net (code "56") (name "unconnected-(IC3-EN0RXIN-Pad53)") (class "Default")
      (node (ref "IC3") (pin "53") (pinfunction "EN0RXIN_53") (pintype "bidirectional"))
    )
    (net (code "57") (name "unconnected-(IC3-EN0RXIP-Pad54)") (class "Default")
      (node (ref "IC3") (pin "54") (pinfunction "EN0RXIP_54") (pintype "bidirectional"))
    )
    (net (code "58") (name "unconnected-(IC3-EN0TXON-Pad56)") (class "Default")
      (node (ref "IC3") (pin "56") (pinfunction "EN0TXON_56") (pintype "bidirectional"))
    )
    (net (code "59") (name "unconnected-(IC3-EN0TXOP-Pad57)") (class "Default")
      (node (ref "IC3") (pin "57") (pinfunction "EN0TXOP_57") (pintype "bidirectional"))
    )
    (net (code "60") (name "unconnected-(IC3-PA3-Pad36)") (class "Default")
      (node (ref "IC3") (pin "36") (pinfunction "PA3_36") (pintype "bidirectional"))
    )
    (net (code "61") (name "unconnected-(IC3-PB0-Pad95)") (class "Default")
      (node (ref "IC3") (pin "95") (pinfunction "PB0_95") (pintype "bidirectional"))
    )
    (net (code "62") (name "unconnected-(IC3-PB1-Pad96)") (class "Default")
      (node (ref "IC3") (pin "96") (pinfunction "PB1_96") (pintype "bidirectional"))
    )
    (net (code "63") (name "unconnected-(IC3-PB2-Pad91)") (class "Default")
      (node (ref "IC3") (pin "91") (pinfunction "PB2_91") (pintype "bidirectional"))
    )
    (net (code "64") (name "unconnected-(IC3-PB3-Pad92)") (class "Default")
      (node (ref "IC3") (pin "92") (pinfunction "PB3_92") (pintype "bidirectional"))
    )
    (net (code "65") (name "unconnected-(IC3-PB4-Pad121)") (class "Default")
      (node (ref "IC3") (pin "121") (pinfunction "PB4_121") (pintype "bidirectional"))
    )
    (net (code "66") (name "unconnected-(IC3-PB5-Pad120)") (class "Default")
      (node (ref "IC3") (pin "120") (pinfunction "PB5_120") (pintype "bidirectional"))
    )
    (net (code "67") (name "unconnected-(IC3-PC4-Pad25)") (class "Default")
      (node (ref "IC3") (pin "25") (pinfunction "PC4_25") (pintype "bidirectional"))
    )
    (net (code "68") (name "unconnected-(IC3-PD0-Pad1)") (class "Default")
      (node (ref "IC3") (pin "1") (pinfunction "PD0_1") (pintype "bidirectional"))
    )
    (net (code "69") (name "unconnected-(IC3-PD1-Pad2)") (class "Default")
      (node (ref "IC3") (pin "2") (pinfunction "PD1_2") (pintype "bidirectional"))
    )
    (net (code "70") (name "unconnected-(IC3-PD2-Pad3)") (class "Default")
      (node (ref "IC3") (pin "3") (pinfunction "PD2_3") (pintype "bidirectional"))
    )
    (net (code "71") (name "unconnected-(IC3-PD3-Pad4)") (class "Default")
      (node (ref "IC3") (pin "4") (pinfunction "PD3_4") (pintype "bidirectional"))
    )
    (net (code "72") (name "unconnected-(IC3-PD4-Pad125)") (class "Default")
      (node (ref "IC3") (pin "125") (pinfunction "PD4_125") (pintype "bidirectional"))
    )
    (net (code "73") (name "unconnected-(IC3-PD5-Pad126)") (class "Default")
      (node (ref "IC3") (pin "126") (pinfunction "PD5_126") (pintype "bidirectional"))
    )
    (net (code "74") (name "unconnected-(IC3-PD6-Pad127)") (class "Default")
      (node (ref "IC3") (pin "127") (pinfunction "PD6_127") (pintype "bidirectional"))
    )
    (net (code "75") (name "unconnected-(IC3-PD7-Pad128)") (class "Default")
      (node (ref "IC3") (pin "128") (pinfunction "PD7_128") (pintype "bidirectional"))
    )
    (net (code "76") (name "unconnected-(IC3-PE0-Pad15)") (class "Default")
      (node (ref "IC3") (pin "15") (pinfunction "PE0_15") (pintype "bidirectional"))
    )
    (net (code "77") (name "unconnected-(IC3-PE1-Pad14)") (class "Default")
      (node (ref "IC3") (pin "14") (pinfunction "PE1_14") (pintype "bidirectional"))
    )
    (net (code "78") (name "unconnected-(IC3-PE2-Pad13)") (class "Default")
      (node (ref "IC3") (pin "13") (pinfunction "PE2_13") (pintype "bidirectional"))
    )
    (net (code "79") (name "unconnected-(IC3-PE4-Pad123)") (class "Default")
      (node (ref "IC3") (pin "123") (pinfunction "PE4_123") (pintype "bidirectional"))
    )
    (net (code "80") (name "unconnected-(IC3-PE5-Pad124)") (class "Default")
      (node (ref "IC3") (pin "124") (pinfunction "PE5_124") (pintype "bidirectional"))
    )
    (net (code "81") (name "unconnected-(IC3-PF0-Pad42)") (class "Default")
      (node (ref "IC3") (pin "42") (pinfunction "PF0_42") (pintype "bidirectional"))
    )
    (net (code "82") (name "unconnected-(IC3-PF1-Pad43)") (class "Default")
      (node (ref "IC3") (pin "43") (pinfunction "PF1_43") (pintype "bidirectional"))
    )
    (net (code "83") (name "unconnected-(IC3-PF2-Pad44)") (class "Default")
      (node (ref "IC3") (pin "44") (pinfunction "PF2_44") (pintype "bidirectional"))
    )
    (net (code "84") (name "unconnected-(IC3-PF3-Pad45)") (class "Default")
      (node (ref "IC3") (pin "45") (pinfunction "PF3_45") (pintype "bidirectional"))
    )
    (net (code "85") (name "unconnected-(IC3-PG0-Pad49)") (class "Default")
      (node (ref "IC3") (pin "49") (pinfunction "PG0_49") (pintype "bidirectional"))
    )
    (net (code "86") (name "unconnected-(IC3-PH2-Pad31)") (class "Default")
      (node (ref "IC3") (pin "31") (pinfunction "PH2_31") (pintype "bidirectional"))
    )
    (net (code "87") (name "unconnected-(IC3-PH3-Pad32)") (class "Default")
      (node (ref "IC3") (pin "32") (pinfunction "PH3_32") (pintype "bidirectional"))
    )
    (net (code "88") (name "unconnected-(IC3-PJ0-Pad116)") (class "Default")
      (node (ref "IC3") (pin "116") (pinfunction "PJ0_116") (pintype "bidirectional"))
    )
    (net (code "89") (name "unconnected-(IC3-PJ1-Pad117)") (class "Default")
      (node (ref "IC3") (pin "117") (pinfunction "PJ1_117") (pintype "bidirectional"))
    )
    (net (code "90") (name "unconnected-(IC3-PK0-Pad18)") (class "Default")
      (node (ref "IC3") (pin "18") (pinfunction "PK0_18") (pintype "bidirectional"))
    )
    (net (code "91") (name "unconnected-(IC3-PK1-Pad19)") (class "Default")
      (node (ref "IC3") (pin "19") (pinfunction "PK1_19") (pintype "bidirectional"))
    )
    (net (code "92") (name "unconnected-(IC3-PK2-Pad20)") (class "Default")
      (node (ref "IC3") (pin "20") (pinfunction "PK2_20") (pintype "bidirectional"))
    )
    (net (code "93") (name "unconnected-(IC3-PL0-Pad81)") (class "Default")
      (node (ref "IC3") (pin "81") (pinfunction "PL0_81") (pintype "bidirectional"))
    )
    (net (code "94") (name "unconnected-(IC3-PL1-Pad82)") (class "Default")
      (node (ref "IC3") (pin "82") (pinfunction "PL1_82") (pintype "bidirectional"))
    )
    (net (code "95") (name "unconnected-(IC3-PL2-Pad83)") (class "Default")
      (node (ref "IC3") (pin "83") (pinfunction "PL2_83") (pintype "bidirectional"))
    )
    (net (code "96") (name "unconnected-(IC3-PL3-Pad84)") (class "Default")
      (node (ref "IC3") (pin "84") (pinfunction "PL3_84") (pintype "bidirectional"))
    )
    (net (code "97") (name "unconnected-(IC3-PL4-Pad85)") (class "Default")
      (node (ref "IC3") (pin "85") (pinfunction "PL4_85") (pintype "bidirectional"))
    )
    (net (code "98") (name "unconnected-(IC3-PL5-Pad86)") (class "Default")
      (node (ref "IC3") (pin "86") (pinfunction "PL5_86") (pintype "bidirectional"))
    )
    (net (code "99") (name "unconnected-(IC3-PL6-Pad94)") (class "Default")
      (node (ref "IC3") (pin "94") (pinfunction "PL6_94") (pintype "bidirectional"))
    )
    (net (code "100") (name "unconnected-(IC3-PL7-Pad93)") (class "Default")
      (node (ref "IC3") (pin "93") (pinfunction "PL7_93") (pintype "bidirectional"))
    )
    (net (code "101") (name "unconnected-(IC3-PM0-Pad78)") (class "Default")
      (node (ref "IC3") (pin "78") (pinfunction "PM0_78") (pintype "bidirectional"))
    )
    (net (code "102") (name "unconnected-(IC3-PM1-Pad77)") (class "Default")
      (node (ref "IC3") (pin "77") (pinfunction "PM1_77") (pintype "bidirectional"))
    )
    (net (code "103") (name "unconnected-(IC3-PM2-Pad76)") (class "Default")
      (node (ref "IC3") (pin "76") (pinfunction "PM2_76") (pintype "bidirectional"))
    )
    (net (code "104") (name "unconnected-(IC3-PM3-Pad75)") (class "Default")
      (node (ref "IC3") (pin "75") (pinfunction "PM3_75") (pintype "bidirectional"))
    )
    (net (code "105") (name "unconnected-(IC3-PM7-Pad71)") (class "Default")
      (node (ref "IC3") (pin "71") (pinfunction "PM7_71") (pintype "bidirectional"))
    )
    (net (code "106") (name "unconnected-(IC3-PN0-Pad107)") (class "Default")
      (node (ref "IC3") (pin "107") (pinfunction "PN0_107") (pintype "bidirectional"))
    )
    (net (code "107") (name "unconnected-(IC3-PN1-Pad108)") (class "Default")
      (node (ref "IC3") (pin "108") (pinfunction "PN1_108") (pintype "bidirectional"))
    )
    (net (code "108") (name "unconnected-(IC3-PN2-Pad109)") (class "Default")
      (node (ref "IC3") (pin "109") (pinfunction "PN2_109") (pintype "bidirectional"))
    )
    (net (code "109") (name "unconnected-(IC3-PN3-Pad110)") (class "Default")
      (node (ref "IC3") (pin "110") (pinfunction "PN3_110") (pintype "bidirectional"))
    )
    (net (code "110") (name "unconnected-(IC3-PN4-Pad111)") (class "Default")
      (node (ref "IC3") (pin "111") (pinfunction "PN4_111") (pintype "bidirectional"))
    )
    (net (code "111") (name "unconnected-(IC3-PN5-Pad112)") (class "Default")
      (node (ref "IC3") (pin "112") (pinfunction "PN5_112") (pintype "bidirectional"))
    )
    (net (code "112") (name "unconnected-(IC3-PP0-Pad118)") (class "Default")
      (node (ref "IC3") (pin "118") (pinfunction "PP0_118") (pintype "bidirectional"))
    )
    (net (code "113") (name "unconnected-(IC3-PP1-Pad119)") (class "Default")
      (node (ref "IC3") (pin "119") (pinfunction "PP1_119") (pintype "bidirectional"))
    )
    (net (code "114") (name "unconnected-(IC3-PP2-Pad103)") (class "Default")
      (node (ref "IC3") (pin "103") (pinfunction "PP2_103") (pintype "bidirectional"))
    )
    (net (code "115") (name "unconnected-(IC3-PP3-Pad104)") (class "Default")
      (node (ref "IC3") (pin "104") (pinfunction "PP3_104") (pintype "bidirectional"))
    )
    (net (code "116") (name "unconnected-(IC3-PP4-Pad105)") (class "Default")
      (node (ref "IC3") (pin "105") (pinfunction "PP4_105") (pintype "bidirectional"))
    )
    (net (code "117") (name "unconnected-(IC3-PP5-Pad106)") (class "Default")
      (node (ref "IC3") (pin "106") (pinfunction "PP5_106") (pintype "bidirectional"))
    )
    (net (code "118") (name "unconnected-(IC3-PQ0-Pad5)") (class "Default")
      (node (ref "IC3") (pin "5") (pinfunction "PQ0_5") (pintype "bidirectional"))
    )
    (net (code "119") (name "unconnected-(IC3-PQ1-Pad6)") (class "Default")
      (node (ref "IC3") (pin "6") (pinfunction "PQ1_6") (pintype "bidirectional"))
    )
    (net (code "120") (name "unconnected-(IC3-PQ2-Pad11)") (class "Default")
      (node (ref "IC3") (pin "11") (pinfunction "PQ2_11") (pintype "bidirectional"))
    )
    (net (code "121") (name "unconnected-(IC3-PQ3-Pad27)") (class "Default")
      (node (ref "IC3") (pin "27") (pinfunction "PQ3_27") (pintype "bidirectional"))
    )
    (net (code "122") (name "unconnected-(IC3-PQ4-Pad102)") (class "Default")
      (node (ref "IC3") (pin "102") (pinfunction "PQ4_102") (pintype "bidirectional"))
    )
    (net (code "123") (name "unconnected-(IC3-VDD11-Pad90)") (class "Default")
      (node (ref "IC3") (pin "90") (pinfunction "VDD11_90") (pintype "bidirectional"))
    )
    (net (code "124") (name "unconnected-(IC3-~{HIB}-Pad65)") (class "Default")
      (node (ref "IC3") (pin "65") (pinfunction "~{HIB}_65") (pintype "bidirectional"))
    )
    (net (code "125") (name "unconnected-(T1-C-Pad3)") (class "Default")
      (node (ref "T1") (pin "3") (pinfunction "C_3") (pintype "passive"))
    )
    (net (code "126") (name "~{RST}") (class "Default")
      (node (ref "IC3") (pin "70") (pinfunction "~{RST}_70") (pintype "bidirectional"))
      (node (ref "J2") (pin "9") (pinfunction "9_9") (pintype "bidirectional"))
      (node (ref "R14") (pin "1") (pinfunction "1_1") (pintype "passive"))
    )
  )
)
